# busy_cube.net
KiCad netlist of a schematic drawn in EAGLE
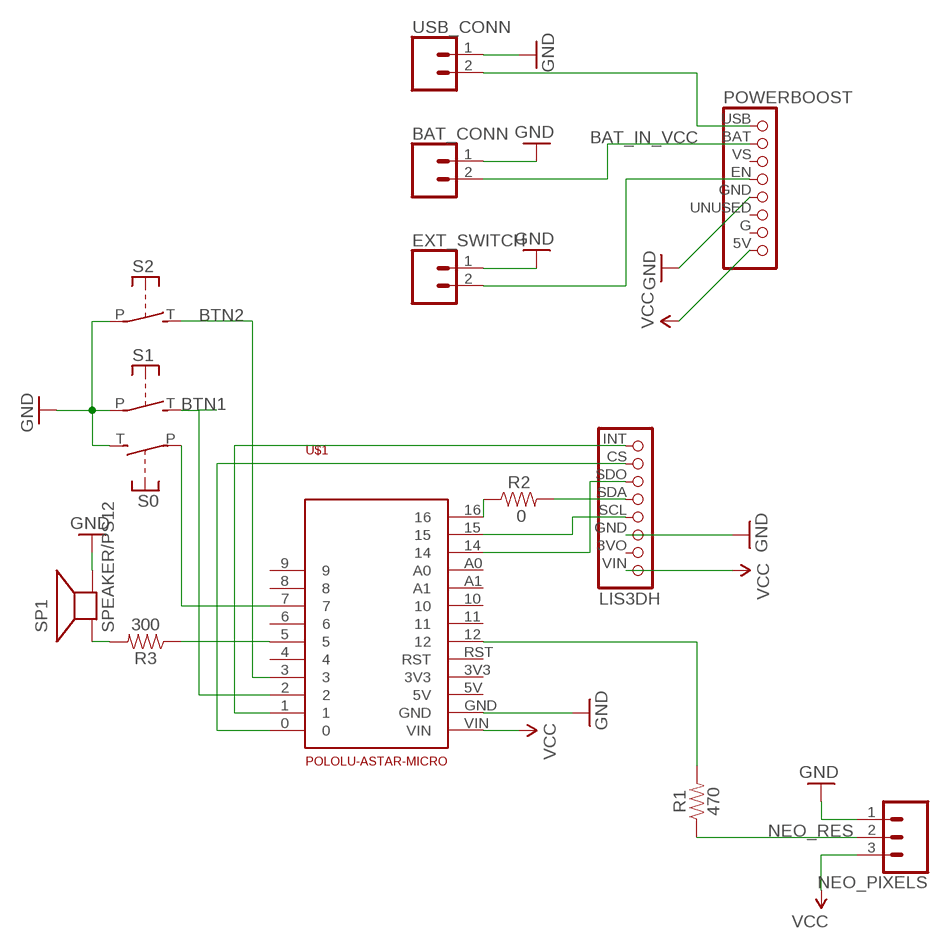
[diagram p0: schematic, sheet 1]

(export (version "E")
  (design (tool "Eeschema 10.0.6"))
  (components
    (comp (ref "BAT_CONN")
      (value "CONN_02-JST-2MM-SMT")
      (footprint "eagle-import:JST-2-SMD")
      (libsource (lib "eagle-import") (part "CONN_02-JST-2MM-SMT"))
    )
    (comp (ref "EXT_SWITCH")
      (value "CONN_02-JST-2MM-SMT")
      (footprint "eagle-import:JST-2-SMD")
      (libsource (lib "eagle-import") (part "CONN_02-JST-2MM-SMT"))
    )
    (comp (ref "LIS3DH")
      (value "ADA-LIS3DHPADS_ONLY")
      (footprint "eagle-import:LIS3DH-1X08")
      (libsource (lib "eagle-import") (part "ADA-LIS3DHPADS_ONLY"))
    )
    (comp (ref "NEO_PIXELS")
      (value "CONN_03LONGPADS")
      (footprint "eagle-import:1X03_LONGPADS")
      (libsource (lib "eagle-import") (part "CONN_03LONGPADS"))
    )
    (comp (ref "POWERBOOST")
      (value "ADA-POWERBOOST-1000CPADS-ONLY")
      (footprint "eagle-import:POWERBOOST-1X08")
      (libsource (lib "eagle-import") (part "ADA-POWERBOOST-1000CPADS-ONLY"))
    )
    (comp (ref "R1")
      (value "470")
      (footprint "eagle-import:AXIAL-0.3")
      (libsource (lib "eagle-import") (part "RESISTORAXIAL-0.3"))
    )
    (comp (ref "R2")
      (value "0")
      (footprint "eagle-import:1206")
      (libsource (lib "eagle-import") (part "RESISTOR1206"))
    )
    (comp (ref "R3")
      (value "300")
      (footprint "eagle-import:AXIAL-0.3")
      (libsource (lib "eagle-import") (part "RESISTORAXIAL-0.3"))
    )
    (comp (ref "S0")
      (value "ADA-ARCADE-BTN30MM")
      (footprint "eagle-import:ARCADE-BTN-30MM")
      (libsource (lib "eagle-import") (part "ADA-ARCADE-BTN30MM"))
    )
    (comp (ref "S1")
      (value "ADA-ARCADE-BTN30MM")
      (footprint "eagle-import:ARCADE-BTN-30MM")
      (libsource (lib "eagle-import") (part "ADA-ARCADE-BTN30MM"))
    )
    (comp (ref "S2")
      (value "ADA-ARCADE-BTN30MM")
      (footprint "eagle-import:ARCADE-BTN-30MM")
      (libsource (lib "eagle-import") (part "ADA-ARCADE-BTN30MM"))
    )
    (comp (ref "SP1")
      (value "SPEAKER/PS12")
      (footprint "eagle-import:PS12")
      (libsource (lib "eagle-import") (part "SPEAKER/PS12"))
    )
    (comp (ref "U$1")
      (value "POLOLU-ASTAR-MICRO")
      (footprint "eagle-import:POLOLU-ASTAR-MICRO")
      (libsource (lib "eagle-import") (part "POLOLU-ASTAR-MICRO"))
    )
    (comp (ref "USB_CONN")
      (value "CONN_02-JST-2MM-SMT")
      (footprint "eagle-import:JST-2-SMD")
      (libsource (lib "eagle-import") (part "CONN_02-JST-2MM-SMT"))
    )
  )
  (nets
    (net (code "1") (name "/3V3") (class "Default")
      (node (ref "U$1") (pin "3V3") (pinfunction "3V3_3V3") (pintype "power_in"))
    )
    (net (code "2") (name "/5V") (class "Default")
      (node (ref "U$1") (pin "5V") (pinfunction "5V_5V") (pintype "power_in"))
    )
    (net (code "3") (name "/BAT_IN_VCC") (class "Default")
      (node (ref "BAT_CONN") (pin "2") (pinfunction "1_2") (pintype "passive"))
      (node (ref "POWERBOOST") (pin "BAT") (pinfunction "3VO_BAT") (pintype "passive"))
    )
    (net (code "4") (name "/BTN1") (class "Default")
      (node (ref "S1") (pin "T") (pinfunction "S_T") (pintype "passive"))
      (node (ref "U$1") (pin "2") (pinfunction "2_2") (pintype "bidirectional"))
    )
    (net (code "5") (name "/BTN2") (class "Default")
      (node (ref "S2") (pin "T") (pinfunction "S_T") (pintype "passive"))
      (node (ref "U$1") (pin "3") (pinfunction "3_3") (pintype "bidirectional"))
    )
    (net (code "6") (name "/NEO_RES") (class "Default")
      (node (ref "NEO_PIXELS") (pin "2") (pinfunction "2_2") (pintype "passive"))
      (node (ref "R1") (pin "P$1") (pinfunction "1_P$1") (pintype "passive"))
    )
    (net (code "7") (name "GND") (class "Default")
      (node (ref "BAT_CONN") (pin "1") (pinfunction "2_1") (pintype "passive"))
      (node (ref "EXT_SWITCH") (pin "1") (pinfunction "2_1") (pintype "passive"))
      (node (ref "LIS3DH") (pin "GND") (pinfunction "GND_GND") (pintype "passive"))
      (node (ref "NEO_PIXELS") (pin "1") (pinfunction "1_1") (pintype "passive"))
      (node (ref "POWERBOOST") (pin "GND") (pinfunction "SDA_GND") (pintype "passive"))
      (node (ref "S0") (pin "T") (pinfunction "S_T") (pintype "passive"))
      (node (ref "S1") (pin "P") (pinfunction "P_P") (pintype "passive"))
      (node (ref "S2") (pin "P") (pinfunction "P_P") (pintype "passive"))
      (node (ref "SP1") (pin "P$2") (pinfunction "-_P$2") (pintype "passive"))
      (node (ref "U$1") (pin "GND") (pinfunction "GND_GND") (pintype "power_in"))
      (node (ref "USB_CONN") (pin "1") (pinfunction "2_1") (pintype "passive"))
    )
    (net (code "8") (name "Net-(EXT_SWITCH-1)") (class "Default")
      (node (ref "EXT_SWITCH") (pin "2") (pinfunction "1_2") (pintype "passive"))
      (node (ref "POWERBOOST") (pin "EN") (pinfunction "SCL_EN") (pintype "passive"))
    )
    (net (code "9") (name "Net-(LIS3DH-PadCS)") (class "Default")
      (node (ref "LIS3DH") (pin "CS") (pinfunction "CS_CS") (pintype "passive"))
      (node (ref "U$1") (pin "0") (pinfunction "0_0") (pintype "bidirectional"))
    )
    (net (code "10") (name "Net-(LIS3DH-PadINT)") (class "Default")
      (node (ref "LIS3DH") (pin "INT") (pinfunction "INT_INT") (pintype "passive"))
      (node (ref "U$1") (pin "1") (pinfunction "1_1") (pintype "bidirectional"))
    )
    (net (code "11") (name "Net-(LIS3DH-PadSCL)") (class "Default")
      (node (ref "LIS3DH") (pin "SCL") (pinfunction "SCL_SCL") (pintype "passive"))
      (node (ref "U$1") (pin "15") (pinfunction "15_15") (pintype "bidirectional"))
    )
    (net (code "12") (name "Net-(LIS3DH-PadSDA)") (class "Default")
      (node (ref "LIS3DH") (pin "SDA") (pinfunction "SDA_SDA") (pintype "passive"))
      (node (ref "R2") (pin "2") (pinfunction "2_2") (pintype "passive"))
    )
    (net (code "13") (name "Net-(LIS3DH-PadSDO)") (class "Default")
      (node (ref "LIS3DH") (pin "SDO") (pinfunction "SDO_SDO") (pintype "passive"))
      (node (ref "U$1") (pin "14") (pinfunction "14_14") (pintype "bidirectional"))
    )
    (net (code "14") (name "Net-(POWERBOOST-VIN)") (class "Default")
      (node (ref "POWERBOOST") (pin "USB") (pinfunction "VIN_USB") (pintype "passive"))
      (node (ref "USB_CONN") (pin "2") (pinfunction "1_2") (pintype "passive"))
    )
    (net (code "15") (name "Net-(R1-2)") (class "Default")
      (node (ref "R1") (pin "P$2") (pinfunction "2_P$2") (pintype "passive"))
      (node (ref "U$1") (pin "12") (pinfunction "12_12") (pintype "bidirectional"))
    )
    (net (code "16") (name "Net-(R2-Pad1)") (class "Default")
      (node (ref "R2") (pin "1") (pinfunction "1_1") (pintype "passive"))
      (node (ref "U$1") (pin "16") (pinfunction "16_16") (pintype "bidirectional"))
    )
    (net (code "17") (name "Net-(R3-1)") (class "Default")
      (node (ref "R3") (pin "P$1") (pinfunction "1_P$1") (pintype "passive"))
      (node (ref "U$1") (pin "5") (pinfunction "5_5") (pintype "bidirectional"))
    )
    (net (code "18") (name "Net-(R3-2)") (class "Default")
      (node (ref "R3") (pin "P$2") (pinfunction "2_P$2") (pintype "passive"))
      (node (ref "SP1") (pin "P$1") (pinfunction "+_P$1") (pintype "passive"))
    )
    (net (code "19") (name "Net-(S0-PadP)") (class "Default")
      (node (ref "S0") (pin "P") (pinfunction "P_P") (pintype "passive"))
      (node (ref "U$1") (pin "7") (pinfunction "7_7") (pintype "bidirectional"))
    )
    (net (code "20") (name "VCC") (class "Default")
      (node (ref "LIS3DH") (pin "VIN") (pinfunction "VIN_VIN") (pintype "passive"))
      (node (ref "NEO_PIXELS") (pin "3") (pinfunction "3_3") (pintype "passive"))
      (node (ref "POWERBOOST") (pin "5V") (pinfunction "INT_5V") (pintype "passive"))
      (node (ref "U$1") (pin "VIN") (pinfunction "VIN_VIN") (pintype "power_in"))
    )
    (net (code "21") (name "unconnected-(LIS3DH-Pad3VO)") (class "Default")
      (node (ref "LIS3DH") (pin "3VO") (pinfunction "3VO_3VO") (pintype "passive"))
    )
    (net (code "22") (name "unconnected-(POWERBOOST-CS-PadG)") (class "Default")
      (node (ref "POWERBOOST") (pin "G") (pinfunction "CS_G") (pintype "passive"))
    )
    (net (code "23") (name "unconnected-(POWERBOOST-GND-PadVS)") (class "Default")
      (node (ref "POWERBOOST") (pin "VS") (pinfunction "GND_VS") (pintype "passive"))
    )
    (net (code "24") (name "unconnected-(POWERBOOST-SDO-PadUNUSED)") (class "Default")
      (node (ref "POWERBOOST") (pin "UNUSED") (pinfunction "SDO_UNUSED") (pintype "passive"))
    )
    (net (code "25") (name "unconnected-(U$1-Pad4)") (class "Default")
      (node (ref "U$1") (pin "4") (pinfunction "4_4") (pintype "bidirectional"))
    )
    (net (code "26") (name "unconnected-(U$1-Pad6)") (class "Default")
      (node (ref "U$1") (pin "6") (pinfunction "6_6") (pintype "bidirectional"))
    )
    (net (code "27") (name "unconnected-(U$1-Pad8)") (class "Default")
      (node (ref "U$1") (pin "8") (pinfunction "8_8") (pintype "bidirectional"))
    )
    (net (code "28") (name "unconnected-(U$1-Pad9)") (class "Default")
      (node (ref "U$1") (pin "9") (pinfunction "9_9") (pintype "bidirectional"))
    )
    (net (code "29") (name "unconnected-(U$1-Pad10)") (class "Default")
      (node (ref "U$1") (pin "10") (pinfunction "10_10") (pintype "bidirectional"))
    )
    (net (code "30") (name "unconnected-(U$1-Pad11)") (class "Default")
      (node (ref "U$1") (pin "11") (pinfunction "11_11") (pintype "bidirectional"))
    )
    (net (code "31") (name "unconnected-(U$1-PadA0)") (class "Default")
      (node (ref "U$1") (pin "A0") (pinfunction "A0_A0") (pintype "bidirectional"))
    )
    (net (code "32") (name "unconnected-(U$1-PadA1)") (class "Default")
      (node (ref "U$1") (pin "A1") (pinfunction "A1_A1") (pintype "bidirectional"))
    )
    (net (code "33") (name "unconnected-(U$1-PadRST)") (class "Default")
      (node (ref "U$1") (pin "RST") (pinfunction "RST_RST") (pintype "input"))
    )
  )
)
